# 318_PCB_FOR.net
KiCad netlist of a schematic drawn in EAGLE
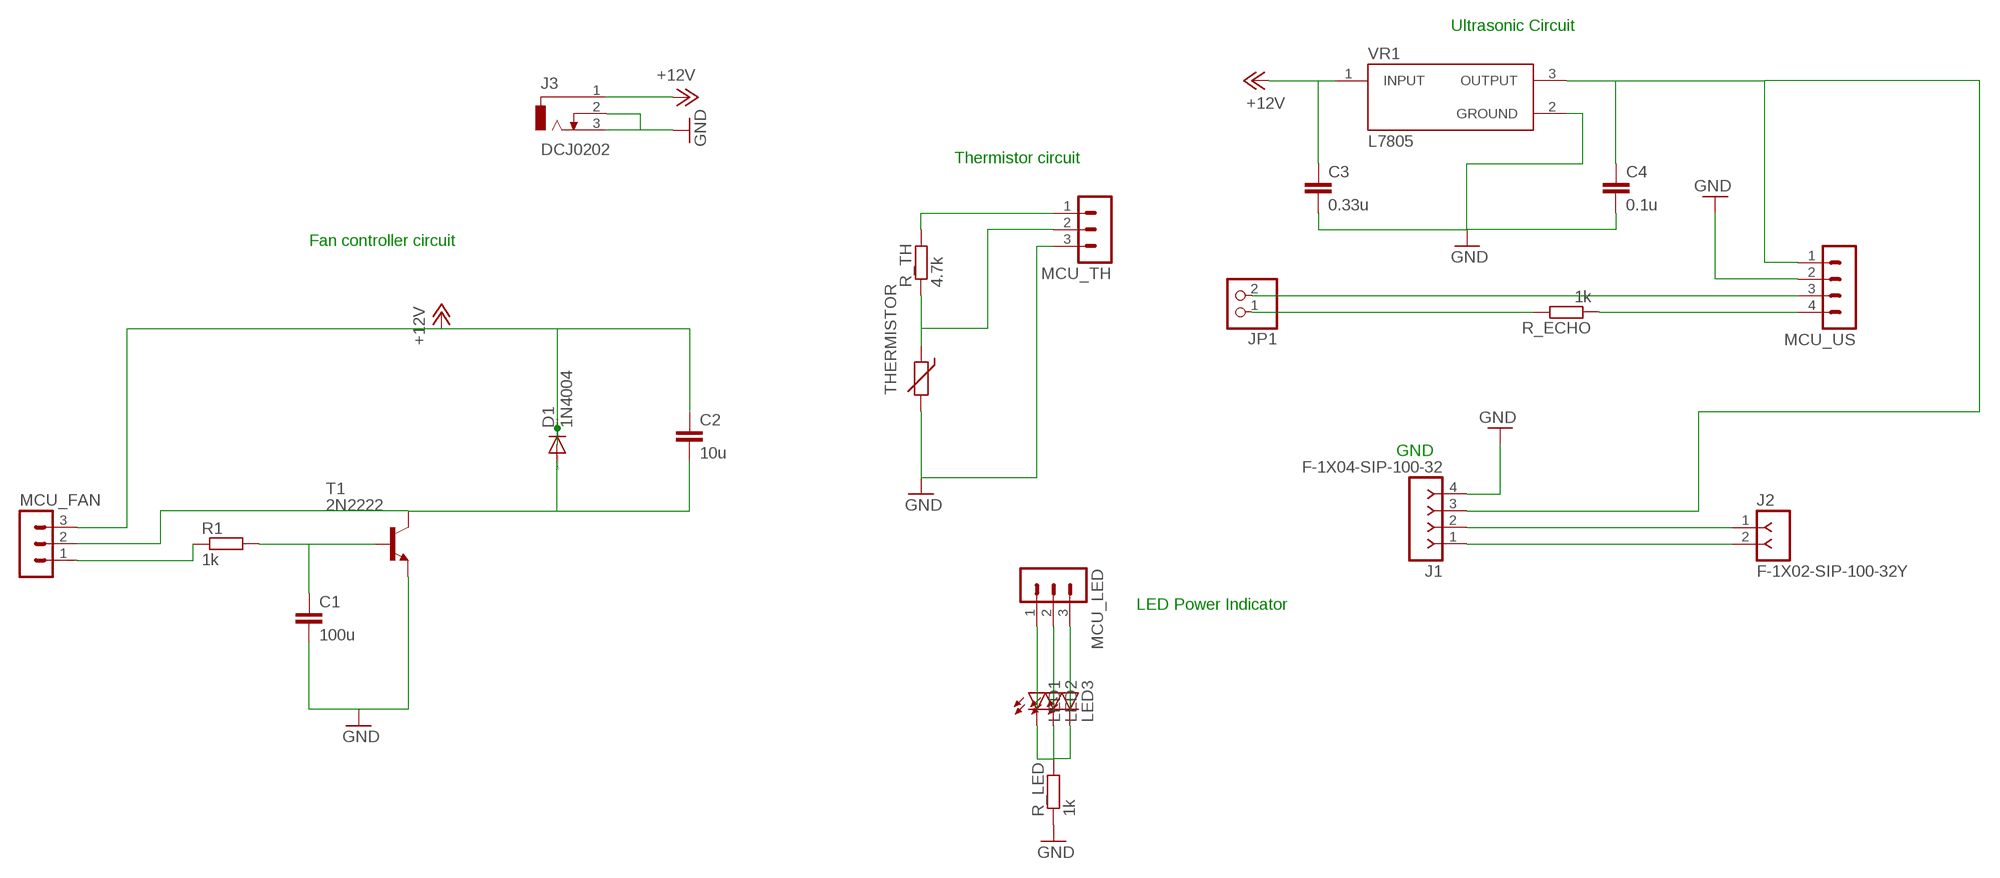
[diagram p0: schematic, sheet 1]

(export (version "E")
  (design (tool "Eeschema 10.0.6"))
  (components
    (comp (ref "C1")
      (value "100u")
      (footprint "eagle-import:C025-025X050")
      (libsource (lib "eagle-import") (part "C-EU025-025X050"))
    )
    (comp (ref "C2")
      (value "10u")
      (footprint "eagle-import:C025-025X050")
      (libsource (lib "eagle-import") (part "C-EU025-025X050"))
    )
    (comp (ref "C3")
      (value "0.33u")
      (footprint "eagle-import:C025-025X050")
      (libsource (lib "eagle-import") (part "C-EU025-025X050"))
    )
    (comp (ref "C4")
      (value "0.1u")
      (footprint "eagle-import:C025-025X050")
      (libsource (lib "eagle-import") (part "C-EU025-025X050"))
    )
    (comp (ref "D1")
      (value "1N4004")
      (footprint "eagle-import:DO41-10")
      (libsource (lib "eagle-import") (part "1N4004"))
    )
    (comp (ref "J1")
      (value "F-1X04-SIP-100-32")
      (footprint "eagle-import:SIP-100-04-32")
      (libsource (lib "eagle-import") (part "F-1X04-SIP-100-32"))
    )
    (comp (ref "J2")
      (value "F-1X02-SIP-100-32Y")
      (footprint "eagle-import:SIP-100-02-32Y")
      (libsource (lib "eagle-import") (part "F-1X02-SIP-100-32Y"))
    )
    (comp (ref "J3")
      (value "DCJ0202")
      (footprint "eagle-import:DCJ0202")
      (libsource (lib "eagle-import") (part "DCJ0202"))
    )
    (comp (ref "JP1")
      (value "PINHD-1X2")
      (footprint "eagle-import:1X02")
      (libsource (lib "eagle-import") (part "PINHD-1X2"))
    )
    (comp (ref "LED1")
      (value "LEDSFH480")
      (footprint "eagle-import:SFH480")
      (libsource (lib "eagle-import") (part "LEDSFH480"))
    )
    (comp (ref "LED2")
      (value "LEDSFH480")
      (footprint "eagle-import:SFH480")
      (libsource (lib "eagle-import") (part "LEDSFH480"))
    )
    (comp (ref "LED3")
      (value "LEDSFH480")
      (footprint "eagle-import:SFH480")
      (libsource (lib "eagle-import") (part "LEDSFH480"))
    )
    (comp (ref "MCU_FAN")
      (value "MA03-1")
      (footprint "eagle-import:MA03-1")
      (libsource (lib "eagle-import") (part "MA03-1"))
    )
    (comp (ref "MCU_LED")
      (value "MA03-1")
      (footprint "eagle-import:MA03-1")
      (libsource (lib "eagle-import") (part "MA03-1"))
    )
    (comp (ref "MCU_TH")
      (value "MA03-1")
      (footprint "eagle-import:MA03-1")
      (libsource (lib "eagle-import") (part "MA03-1"))
    )
    (comp (ref "MCU_US")
      (value "MA04-1")
      (footprint "eagle-import:MA04-1")
      (libsource (lib "eagle-import") (part "MA04-1"))
    )
    (comp (ref "R1")
      (value "1k")
      (footprint "eagle-import:0207_10")
      (libsource (lib "eagle-import") (part "R-EU_0207/10"))
    )
    (comp (ref "R_ECHO")
      (value "1k")
      (footprint "eagle-import:0207_10")
      (libsource (lib "eagle-import") (part "R-EU_0207/10"))
    )
    (comp (ref "R_LED")
      (value "1k")
      (footprint "eagle-import:0207_10")
      (libsource (lib "eagle-import") (part "R-EU_0207/10"))
    )
    (comp (ref "R_TH")
      (value "4.7k")
      (footprint "eagle-import:0207_10")
      (libsource (lib "eagle-import") (part "R-EU_0207/10"))
    )
    (comp (ref "T1")
      (value "2N2222")
      (footprint "eagle-import:TO18")
      (libsource (lib "eagle-import") (part "2N2222"))
    )
    (comp (ref "THERMISTOR")
      (value "THERMISTOR-5")
      (footprint "eagle-import:R-5")
      (libsource (lib "eagle-import") (part "THERMISTOR-5"))
    )
    (comp (ref "VR1")
      (value "L7805")
      (footprint "eagle-import:TO255P1020X450X2000-3")
      (fields (field (name "MF") "STMicroelectronics"))
      (libsource (lib "eagle-import") (part "L7805"))
    )
  )
  (nets
    (net (code "1") (name "+12V") (class "Default")
      (node (ref "C2") (pin "1") (pinfunction "1_1") (pintype "passive"))
      (node (ref "C3") (pin "1") (pinfunction "1_1") (pintype "passive"))
      (node (ref "D1") (pin "C") (pinfunction "C_C") (pintype "passive"))
      (node (ref "J3") (pin "1") (pinfunction "1_1") (pintype "passive"))
      (node (ref "MCU_FAN") (pin "3") (pinfunction "3_3") (pintype "passive"))
      (node (ref "VR1") (pin "1") (pinfunction "INPUT_1") (pintype "input"))
    )
    (net (code "2") (name "GND") (class "Default")
      (node (ref "C1") (pin "2") (pinfunction "2_2") (pintype "passive"))
      (node (ref "C3") (pin "2") (pinfunction "2_2") (pintype "passive"))
      (node (ref "C4") (pin "2") (pinfunction "2_2") (pintype "passive"))
      (node (ref "J1") (pin "4") (pinfunction "4_4") (pintype "passive"))
      (node (ref "J3") (pin "2") (pinfunction "2_2") (pintype "passive"))
      (node (ref "J3") (pin "3") (pinfunction "3_3") (pintype "passive"))
      (node (ref "MCU_TH") (pin "3") (pinfunction "3_3") (pintype "passive"))
      (node (ref "MCU_US") (pin "2") (pinfunction "2_2") (pintype "passive"))
      (node (ref "R_LED") (pin "1") (pinfunction "1_1") (pintype "passive"))
      (node (ref "T1") (pin "1") (pinfunction "E_1") (pintype "passive"))
      (node (ref "THERMISTOR") (pin "2") (pinfunction "2_2") (pintype "passive"))
      (node (ref "VR1") (pin "2") (pinfunction "GROUND_2") (pintype "power_in"))
    )
    (net (code "3") (name "Net-(J1-Pad1)") (class "Default")
      (node (ref "J1") (pin "1") (pinfunction "1_1") (pintype "passive"))
      (node (ref "J2") (pin "2") (pinfunction "2_2") (pintype "passive"))
    )
    (net (code "4") (name "Net-(J1-Pad2)") (class "Default")
      (node (ref "J1") (pin "2") (pinfunction "2_2") (pintype "passive"))
      (node (ref "J2") (pin "1") (pinfunction "1_1") (pintype "passive"))
    )
    (net (code "5") (name "Net-(JP1-Pad1)") (class "Default")
      (node (ref "JP1") (pin "1") (pinfunction "1_1") (pintype "passive"))
      (node (ref "R_ECHO") (pin "2") (pinfunction "2_2") (pintype "passive"))
    )
    (net (code "6") (name "Net-(JP1-Pad2)") (class "Default")
      (node (ref "JP1") (pin "2") (pinfunction "2_2") (pintype "passive"))
      (node (ref "MCU_US") (pin "3") (pinfunction "3_3") (pintype "passive"))
    )
    (net (code "7") (name "Net-(LED1-C)") (class "Default")
      (node (ref "LED1") (pin "K") (pinfunction "C_K") (pintype "passive"))
      (node (ref "LED2") (pin "K") (pinfunction "C_K") (pintype "passive"))
      (node (ref "LED3") (pin "K") (pinfunction "C_K") (pintype "passive"))
      (node (ref "R_LED") (pin "2") (pinfunction "2_2") (pintype "passive"))
    )
    (net (code "8") (name "Net-(LED1-PadA)") (class "Default")
      (node (ref "LED1") (pin "A") (pinfunction "A_A") (pintype "passive"))
      (node (ref "MCU_LED") (pin "1") (pinfunction "1_1") (pintype "passive"))
    )
    (net (code "9") (name "Net-(LED2-PadA)") (class "Default")
      (node (ref "LED2") (pin "A") (pinfunction "A_A") (pintype "passive"))
      (node (ref "MCU_LED") (pin "2") (pinfunction "2_2") (pintype "passive"))
    )
    (net (code "10") (name "Net-(LED3-PadA)") (class "Default")
      (node (ref "LED3") (pin "A") (pinfunction "A_A") (pintype "passive"))
      (node (ref "MCU_LED") (pin "3") (pinfunction "3_3") (pintype "passive"))
    )
    (net (code "11") (name "Net-(MCU_FAN-Pad1)") (class "Default")
      (node (ref "MCU_FAN") (pin "1") (pinfunction "1_1") (pintype "passive"))
      (node (ref "R1") (pin "1") (pinfunction "1_1") (pintype "passive"))
    )
    (net (code "12") (name "Net-(MCU_TH-Pad1)") (class "Default")
      (node (ref "MCU_TH") (pin "1") (pinfunction "1_1") (pintype "passive"))
      (node (ref "R_TH") (pin "2") (pinfunction "2_2") (pintype "passive"))
    )
    (net (code "13") (name "Net-(MCU_TH-Pad2)") (class "Default")
      (node (ref "MCU_TH") (pin "2") (pinfunction "2_2") (pintype "passive"))
      (node (ref "R_TH") (pin "1") (pinfunction "1_1") (pintype "passive"))
      (node (ref "THERMISTOR") (pin "1") (pinfunction "1_1") (pintype "passive"))
    )
    (net (code "14") (name "Net-(MCU_US-Pad4)") (class "Default")
      (node (ref "MCU_US") (pin "4") (pinfunction "4_4") (pintype "passive"))
      (node (ref "R_ECHO") (pin "1") (pinfunction "1_1") (pintype "passive"))
    )
    (net (code "15") (name "Net-(T1-B)") (class "Default")
      (node (ref "C1") (pin "1") (pinfunction "1_1") (pintype "passive"))
      (node (ref "R1") (pin "2") (pinfunction "2_2") (pintype "passive"))
      (node (ref "T1") (pin "2") (pinfunction "B_2") (pintype "passive"))
    )
    (net (code "16") (name "Net-(T1-C)") (class "Default")
      (node (ref "C2") (pin "2") (pinfunction "2_2") (pintype "passive"))
      (node (ref "D1") (pin "A") (pinfunction "A_A") (pintype "passive"))
      (node (ref "MCU_FAN") (pin "2") (pinfunction "2_2") (pintype "passive"))
      (node (ref "T1") (pin "3") (pinfunction "C_3") (pintype "passive"))
    )
    (net (code "17") (name "Net-(VR1-OUTPUT)") (class "Default")
      (node (ref "C4") (pin "1") (pinfunction "1_1") (pintype "passive"))
      (node (ref "J1") (pin "3") (pinfunction "3_3") (pintype "passive"))
      (node (ref "MCU_US") (pin "1") (pinfunction "1_1") (pintype "passive"))
      (node (ref "VR1") (pin "3") (pinfunction "OUTPUT_3") (pintype "output"))
    )
  )
)
